# Motortreiber_1_2.net
KiCad netlist of a schematic drawn in Altium Designer
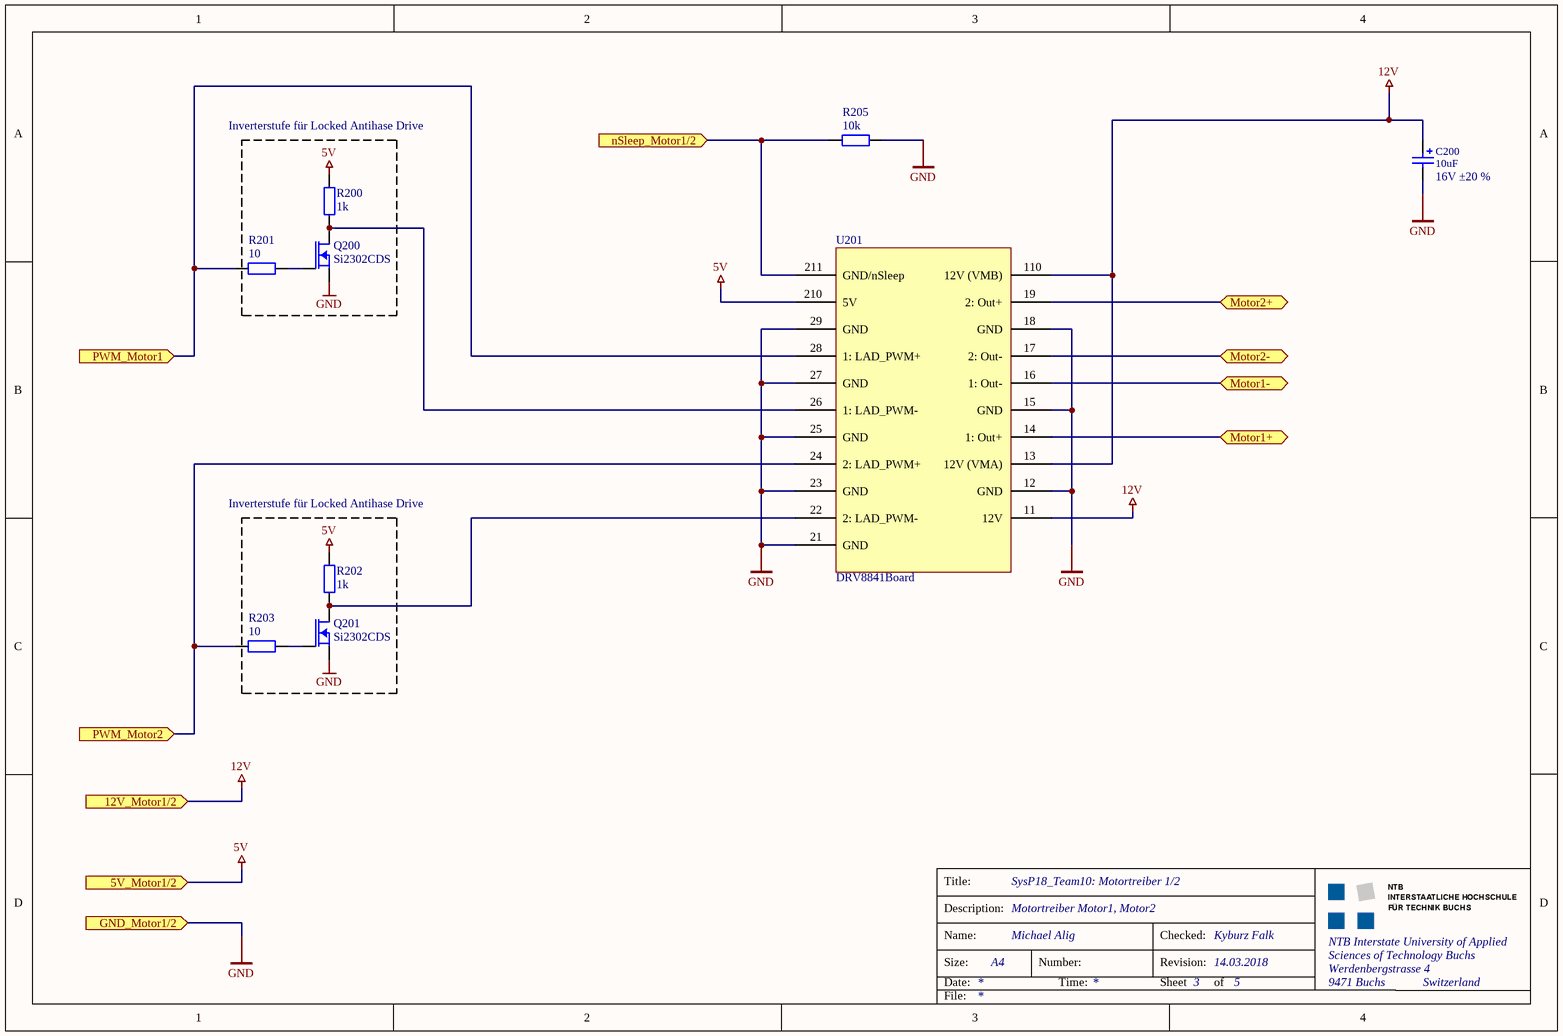
[diagram p0: Motortreiber_1,2.SchDoc]

(export (version "E")
  (design (tool "Eeschema 10.0.6"))
  (components
    (comp (ref "C200")
      (value "10uF")
      (footprint "CDE_CAP AVE CODE D_H")
      (description "Aluminum Electrolytic Capacitors for Filtering and Bypass, 47uF, 16V")
      (fields
        (field (name "MANUFACTURER") "Cornell Dubilier")
        (field (name "VALUEADDON") "16V ±20 %")
        (field (name "Comment") "AVE476M16D16T-F")
        (field (name "PUBLISHER") "Stefan Ursella, M.Eng")
      )
      (libsource (lib "Motorentreiber") (part "CDE_AVE476M16D16T-F_AVE CODE D"))
    )
    (comp (ref "Q200")
      (value "Si2302CDS")
      (footprint "SOT23-3")
      (description "N-Channel 20V (D-S) MOSFET")
      (libsource (lib "Motorentreiber") (part "Depletion Mode MOSFET"))
    )
    (comp (ref "Q201")
      (value "Si2302CDS")
      (footprint "SOT23-3")
      (description "N-Channel 20V (D-S) MOSFET")
      (libsource (lib "Motorentreiber") (part "Depletion Mode MOSFET"))
    )
    (comp (ref "R200")
      (value "1k")
      (footprint "GEN_R0805_H")
      (description "generic resistor")
      (fields
        (field (name "MANUFACTURER") "Tbd")
        (field (name "Comment") "Generic")
        (field (name "PUBLISHER") "Altium Limited")
      )
      (libsource (lib "Motorentreiber") (part "GEN_R_2"))
    )
    (comp (ref "R201")
      (value "10")
      (footprint "GEN_R0805_H")
      (description "generic resistor")
      (fields
        (field (name "MANUFACTURER") "Tbd")
        (field (name "Comment") "Generic")
        (field (name "PUBLISHER") "Altium Limited")
      )
      (libsource (lib "") (part "GEN_R_2_1"))
    )
    (comp (ref "R202")
      (value "1k")
      (footprint "GEN_R0805_H")
      (description "generic resistor")
      (fields
        (field (name "MANUFACTURER") "Tbd")
        (field (name "Comment") "Generic")
        (field (name "PUBLISHER") "Altium Limited")
      )
      (libsource (lib "Motorentreiber") (part "GEN_R_2"))
    )
    (comp (ref "R203")
      (value "10")
      (footprint "GEN_R0805_H")
      (description "generic resistor")
      (fields
        (field (name "MANUFACTURER") "Tbd")
        (field (name "Comment") "Generic")
        (field (name "PUBLISHER") "Altium Limited")
      )
      (libsource (lib "") (part "GEN_R_2_1"))
    )
    (comp (ref "R205")
      (value "10k")
      (footprint "GEN_R0805_H")
      (description "generic resistor")
      (fields
        (field (name "MANUFACTURER") "Tbd")
        (field (name "Comment") "Generic")
        (field (name "PUBLISHER") "Altium Limited")
      )
      (libsource (lib "") (part "GEN_R_2_1"))
    )
    (comp (ref "U201")
      (value "DRV8841Board")
      (footprint "DRV8841_Board")
      (libsource (lib "Motorentreiber") (part "DRV8841_Board"))
    )
  )
  (nets
    (net (code "1") (name "/Motor1+") (class "Default")
      (node (ref "U201") (pin "14") (pinfunction "1:_Out+_14") (pintype "passive"))
    )
    (net (code "2") (name "/Motor1-") (class "Default")
      (node (ref "U201") (pin "16") (pinfunction "1:_Out-_16") (pintype "passive"))
    )
    (net (code "3") (name "/Motor2+") (class "Default")
      (node (ref "U201") (pin "19") (pinfunction "2:_Out+_19") (pintype "passive"))
    )
    (net (code "4") (name "/Motor2-") (class "Default")
      (node (ref "U201") (pin "17") (pinfunction "2:_Out-_17") (pintype "passive"))
    )
    (net (code "5") (name "/PWM_Motor1") (class "Default")
      (node (ref "R201") (pin "1") (pinfunction "1_1") (pintype "passive"))
      (node (ref "U201") (pin "28") (pinfunction "1:_LAD_PWM+_28") (pintype "passive"))
    )
    (net (code "6") (name "/PWM_Motor2") (class "Default")
      (node (ref "R203") (pin "1") (pinfunction "1_1") (pintype "passive"))
      (node (ref "U201") (pin "24") (pinfunction "2:_LAD_PWM+_24") (pintype "passive"))
    )
    (net (code "7") (name "/nSleep_Motor1{slash}2") (class "Default")
      (node (ref "R205") (pin "1") (pinfunction "1_1") (pintype "passive"))
      (node (ref "U201") (pin "211") (pinfunction "GND/nSleep_211") (pintype "passive"))
    )
    (net (code "8") (name "5V") (class "Default")
      (node (ref "R200") (pin "2") (pinfunction "2_2") (pintype "passive"))
      (node (ref "R202") (pin "2") (pinfunction "2_2") (pintype "passive"))
      (node (ref "U201") (pin "210") (pinfunction "5V_210") (pintype "passive"))
    )
    (net (code "9") (name "12V") (class "Default")
      (node (ref "C200") (pin "1") (pinfunction "Pos_1") (pintype "passive"))
      (node (ref "U201") (pin "11") (pinfunction "12V_11") (pintype "passive"))
      (node (ref "U201") (pin "110") (pinfunction "12V_(VMB)_110") (pintype "passive"))
      (node (ref "U201") (pin "13") (pinfunction "12V_(VMA)_13") (pintype "passive"))
    )
    (net (code "10") (name "GND") (class "Default")
      (node (ref "C200") (pin "2") (pinfunction "Neg_2") (pintype "passive"))
      (node (ref "Q200") (pin "2") (pinfunction "S_2") (pintype "passive"))
      (node (ref "Q201") (pin "2") (pinfunction "S_2") (pintype "passive"))
      (node (ref "R205") (pin "2") (pinfunction "2_2") (pintype "passive"))
      (node (ref "U201") (pin "12") (pinfunction "GND_12") (pintype "passive"))
      (node (ref "U201") (pin "15") (pinfunction "GND_15") (pintype "passive"))
      (node (ref "U201") (pin "18") (pinfunction "GND_18") (pintype "passive"))
      (node (ref "U201") (pin "21") (pinfunction "GND_21") (pintype "passive"))
      (node (ref "U201") (pin "23") (pinfunction "GND_23") (pintype "passive"))
      (node (ref "U201") (pin "25") (pinfunction "GND_25") (pintype "passive"))
      (node (ref "U201") (pin "27") (pinfunction "GND_27") (pintype "passive"))
      (node (ref "U201") (pin "29") (pinfunction "GND_29") (pintype "passive"))
    )
    (net (code "11") (name "Net-(Q200-D)") (class "Default")
      (node (ref "Q200") (pin "3") (pinfunction "D_3") (pintype "passive"))
      (node (ref "R200") (pin "1") (pinfunction "1_1") (pintype "passive"))
      (node (ref "U201") (pin "26") (pinfunction "1:_LAD_PWM-_26") (pintype "passive"))
    )
    (net (code "12") (name "Net-(Q200-G)") (class "Default")
      (node (ref "Q200") (pin "1") (pinfunction "G_1") (pintype "passive"))
      (node (ref "R201") (pin "2") (pinfunction "2_2") (pintype "passive"))
    )
    (net (code "13") (name "Net-(Q201-D)") (class "Default")
      (node (ref "Q201") (pin "3") (pinfunction "D_3") (pintype "passive"))
      (node (ref "R202") (pin "1") (pinfunction "1_1") (pintype "passive"))
      (node (ref "U201") (pin "22") (pinfunction "2:_LAD_PWM-_22") (pintype "passive"))
    )
    (net (code "14") (name "Net-(Q201-G)") (class "Default")
      (node (ref "Q201") (pin "1") (pinfunction "G_1") (pintype "passive"))
      (node (ref "R203") (pin "2") (pinfunction "2_2") (pintype "passive"))
    )
  )
)
